# Sensors.net
KiCad netlist of a schematic drawn in Altium Designer
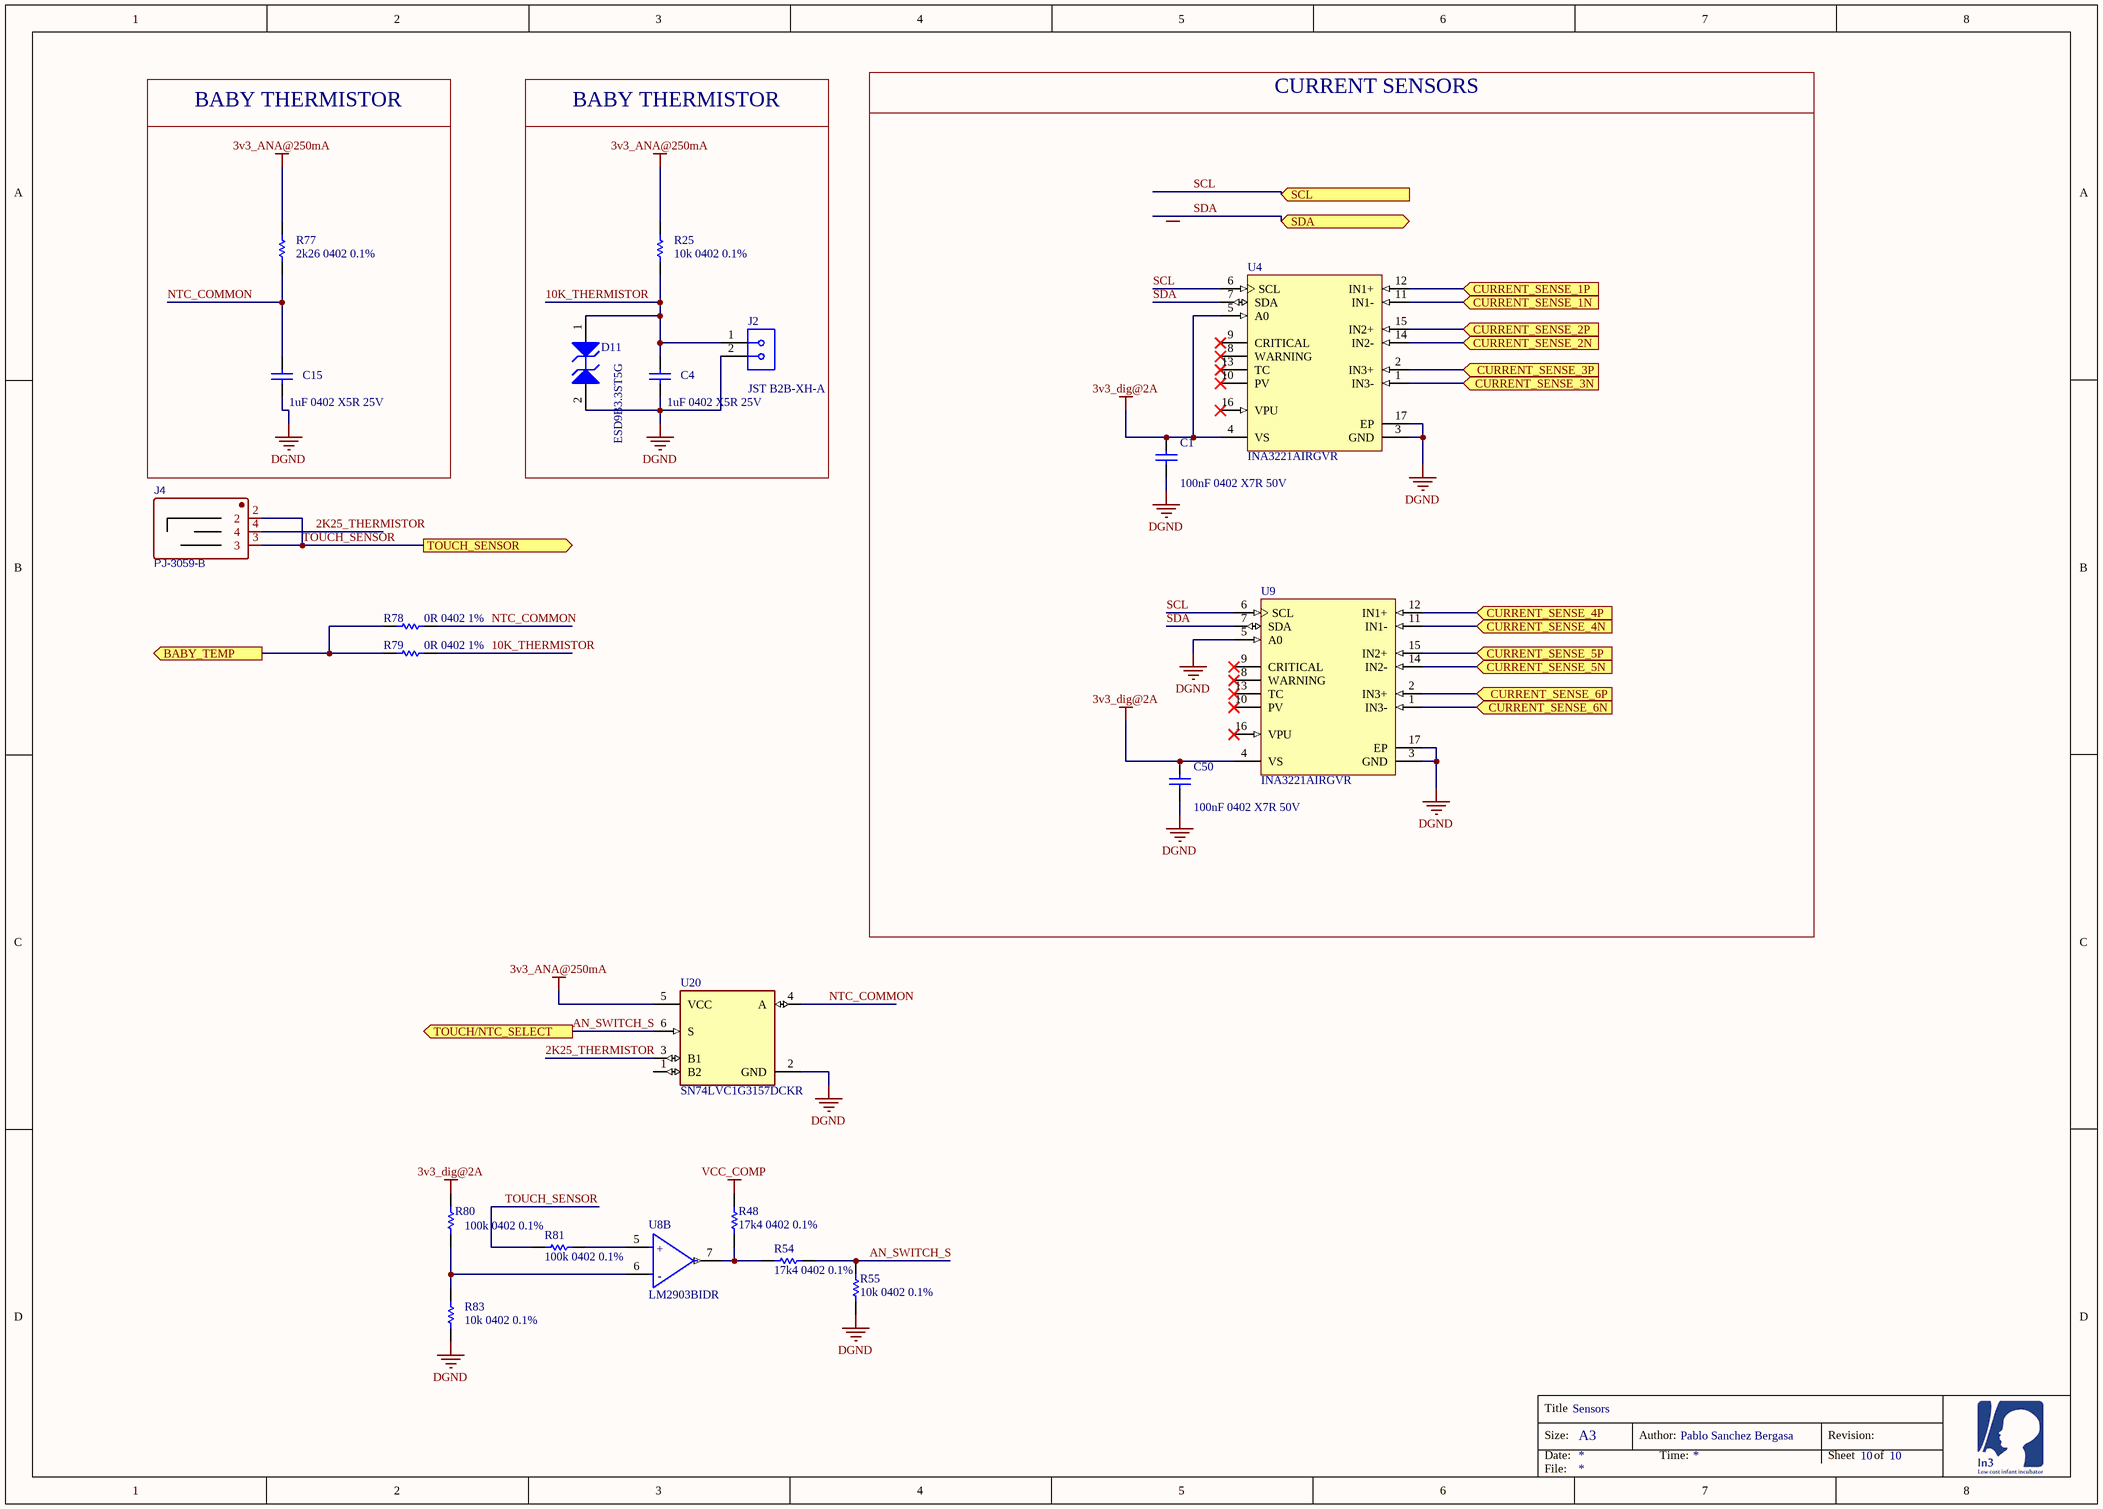
[diagram p0: Sensors.SchDoc]

(export (version "E")
  (design (tool "Eeschema 10.0.6"))
  (components
    (comp (ref "C1")
      (value "100nF 0402 X7R 50V")
      (footprint "CAPC1005X55X25NL5T10")
      (libsource (lib "Altium Content Vault") (part "CAP-NP-2"))
    )
    (comp (ref "C4")
      (value "1uF 0402 X5R 25V")
      (footprint "CAPC1005X55X25NL5T10")
      (libsource (lib "Altium Content Vault") (part "CAP-NP-2"))
    )
    (comp (ref "C15")
      (value "1uF 0402 X5R 25V")
      (footprint "CAPC1005X55X25NL5T10")
      (libsource (lib "Altium Content Vault") (part "CAP-NP-2"))
    )
    (comp (ref "C50")
      (value "100nF 0402 X7R 50V")
      (footprint "CAPC1005X55X25NL5T10")
      (libsource (lib "Altium Content Vault") (part "CAP-NP-2"))
    )
    (comp (ref "D11")
      (value "ESD9B3.3ST5G")
      (footprint "ONSC-SOD-923-2-514AB-01_V")
      (fields (field (name "MANUFACTURER") "On Semiconductor"))
      (libsource (lib "Altium Content Vault") (part "ONSC-A1A2-2"))
    )
    (comp (ref "J2")
      (value "JST B2B-XH-A")
      (footprint "PCB-pp1at3pfx7vls1ur72ey-1")
      (description "Conn Shrouded Header HDR 2 POS 2.5mm Solder ST Thru-Hole Box")
      (fields (field (name "MANUFACTURER PART NUMBER") "B2B-XH-A") (field (name "LCSC PART") "C158012"))
      (libsource (lib "in3ator") (part "CMP-1d67d451da9ec2a0-3"))
    )
    (comp (ref "J4")
      (value "PJ-3059-B")
      (footprint "PJ-3059-B")
      (libsource (lib "jlcpcb_components") (part "PJ-3059-B"))
    )
    (comp (ref "R25")
      (value "10k 0402 0.1%")
      (footprint "RESC1005X40X25ML05T10")
      (libsource (lib "Altium Content Vault") (part "RES"))
    )
    (comp (ref "R48")
      (value "17k4 0402 0.1%")
      (footprint "RESC1005X40X25ML05T10")
      (libsource (lib "Altium Content Vault") (part "RES"))
    )
    (comp (ref "R54")
      (value "17k4 0402 0.1%")
      (footprint "RESC1005X40X25ML05T10")
      (libsource (lib "Altium Content Vault") (part "RES"))
    )
    (comp (ref "R55")
      (value "10k 0402 0.1%")
      (footprint "RESC1005X40X25ML05T10")
      (libsource (lib "Altium Content Vault") (part "RES"))
    )
    (comp (ref "R77")
      (value "2k26 0402 0.1%")
      (footprint "RESC1005X40X25ML05T10")
      (libsource (lib "Altium Content Vault") (part "RES"))
    )
    (comp (ref "R78")
      (value "0R 0402 1%")
      (footprint "RESC1005X40X25ML05T10")
      (libsource (lib "Altium Content Vault") (part "RES"))
    )
    (comp (ref "R79")
      (value "0R 0402 1%")
      (footprint "RESC1005X40X25ML05T10")
      (libsource (lib "Altium Content Vault") (part "RES"))
    )
    (comp (ref "R80")
      (value "100k 0402 0.1%")
      (footprint "RESC1005X40X25ML05T10")
      (libsource (lib "Altium Content Vault") (part "RES"))
    )
    (comp (ref "R81")
      (value "100k 0402 0.1%")
      (footprint "RESC1005X40X25ML05T10")
      (libsource (lib "Altium Content Vault") (part "RES"))
    )
    (comp (ref "R83")
      (value "10k 0402 0.1%")
      (footprint "RESC1005X40X25ML05T10")
      (libsource (lib "Altium Content Vault") (part "RES"))
    )
    (comp (ref "U4")
      (value "INA3221AIRGVR")
      (footprint "RGV0016A_V")
      (fields (field (name "MANUFACTURER") "Texas Instruments"))
      (libsource (lib "Altium Content Vault") (part "TI-INA3221-RGV-16"))
    )
    (comp (ref "U8")
      (value "LM2903BIDR")
      (footprint "FP-D0008A-MFG")
      (description "36V JI.3 DUAL COMPARATOR")
      (fields
        (field (name "OCTOPART") "https://octopart.com/lm2903bidr-texas+instruments-104977165")
        (field (name "MANUFACTURER") "Texas Instruments")
      )
      (libsource (lib "Altium Content Vault") (part "d0dfe35d032f86ae96c0c3919f86c94"))
    )
    (comp (ref "U9")
      (value "INA3221AIRGVR")
      (footprint "RGV0016A_V")
      (fields (field (name "MANUFACTURER") "Texas Instruments"))
      (libsource (lib "Altium Content Vault") (part "TI-INA3221-RGV-16"))
    )
    (comp (ref "U20")
      (value "SN74LVC1G3157DCKR")
      (footprint "FP-DCK0006A-IPC_B")
      (description "IC SWITCH SPDT SC70-6")
      (libsource (lib "Altium Content Vault") (part "0261a57985ab8eeec66806cf7caee19"))
    )
  )
  (nets
    (net (code "1") (name "/2K25_THERMISTOR") (class "Default")
      (node (ref "J4") (pin "4") (pinfunction "4_4") (pintype "passive"))
      (node (ref "U20") (pin "3") (pinfunction "B1_3") (pintype "bidirectional"))
    )
    (net (code "2") (name "/10K_THERMISTOR") (class "Default")
      (node (ref "C4") (pin "2") (pinfunction "2_2") (pintype "passive"))
      (node (ref "D11") (pin "1") (pinfunction "A1_1") (pintype "passive"))
      (node (ref "J2") (pin "1") (pinfunction "1_1") (pintype "passive"))
      (node (ref "R25") (pin "1") (pinfunction "1_1") (pintype "passive"))
      (node (ref "R79") (pin "1") (pinfunction "1_1") (pintype "passive"))
    )
    (net (code "3") (name "/AN_SWITCH_S") (class "Default")
      (node (ref "R54") (pin "2") (pinfunction "2_2") (pintype "passive"))
      (node (ref "R55") (pin "1") (pinfunction "1_1") (pintype "passive"))
      (node (ref "U20") (pin "6") (pinfunction "S_6") (pintype "input"))
    )
    (net (code "4") (name "/BABY_TEMP") (class "Default")
      (node (ref "R78") (pin "2") (pinfunction "2_2") (pintype "passive"))
      (node (ref "R79") (pin "2") (pinfunction "2_2") (pintype "passive"))
    )
    (net (code "5") (name "/CURRENT_SENSE_1N") (class "Default")
      (node (ref "U4") (pin "11") (pinfunction "IN1-_11") (pintype "input"))
    )
    (net (code "6") (name "/CURRENT_SENSE_1P") (class "Default")
      (node (ref "U4") (pin "12") (pinfunction "IN1+_12") (pintype "input"))
    )
    (net (code "7") (name "/CURRENT_SENSE_2N") (class "Default")
      (node (ref "U4") (pin "14") (pinfunction "IN2-_14") (pintype "input"))
    )
    (net (code "8") (name "/CURRENT_SENSE_2P") (class "Default")
      (node (ref "U4") (pin "15") (pinfunction "IN2+_15") (pintype "input"))
    )
    (net (code "9") (name "/CURRENT_SENSE_3N") (class "Default")
      (node (ref "U4") (pin "1") (pinfunction "IN3-_1") (pintype "input"))
    )
    (net (code "10") (name "/CURRENT_SENSE_3P") (class "Default")
      (node (ref "U4") (pin "2") (pinfunction "IN3+_2") (pintype "input"))
    )
    (net (code "11") (name "/CURRENT_SENSE_4N") (class "Default")
      (node (ref "U9") (pin "11") (pinfunction "IN1-_11") (pintype "input"))
    )
    (net (code "12") (name "/CURRENT_SENSE_4P") (class "Default")
      (node (ref "U9") (pin "12") (pinfunction "IN1+_12") (pintype "input"))
    )
    (net (code "13") (name "/CURRENT_SENSE_5N") (class "Default")
      (node (ref "U9") (pin "14") (pinfunction "IN2-_14") (pintype "input"))
    )
    (net (code "14") (name "/CURRENT_SENSE_5P") (class "Default")
      (node (ref "U9") (pin "15") (pinfunction "IN2+_15") (pintype "input"))
    )
    (net (code "15") (name "/CURRENT_SENSE_6N") (class "Default")
      (node (ref "U9") (pin "1") (pinfunction "IN3-_1") (pintype "input"))
    )
    (net (code "16") (name "/CURRENT_SENSE_6P") (class "Default")
      (node (ref "U9") (pin "2") (pinfunction "IN3+_2") (pintype "input"))
    )
    (net (code "17") (name "/NTC_COMMON") (class "Default")
      (node (ref "C15") (pin "2") (pinfunction "2_2") (pintype "passive"))
      (node (ref "R77") (pin "1") (pinfunction "1_1") (pintype "passive"))
      (node (ref "R78") (pin "1") (pinfunction "1_1") (pintype "passive"))
      (node (ref "U20") (pin "4") (pinfunction "A_4") (pintype "bidirectional"))
    )
    (net (code "18") (name "/SCL") (class "Default")
      (node (ref "U4") (pin "6") (pinfunction "SCL_6") (pintype "input"))
      (node (ref "U9") (pin "6") (pinfunction "SCL_6") (pintype "input"))
    )
    (net (code "19") (name "/SDA") (class "Default")
      (node (ref "U4") (pin "7") (pinfunction "SDA_7") (pintype "bidirectional"))
      (node (ref "U9") (pin "7") (pinfunction "SDA_7") (pintype "bidirectional"))
    )
    (net (code "20") (name "/TOUCH_SENSOR") (class "Default")
      (node (ref "J4") (pin "2") (pinfunction "2_2") (pintype "passive"))
      (node (ref "J4") (pin "3") (pinfunction "3_3") (pintype "passive"))
      (node (ref "R81") (pin "2") (pinfunction "2_2") (pintype "passive"))
    )
    (net (code "21") (name "3v3_ANA@250mA") (class "Default")
      (node (ref "R25") (pin "2") (pinfunction "2_2") (pintype "passive"))
      (node (ref "R77") (pin "2") (pinfunction "2_2") (pintype "passive"))
      (node (ref "U20") (pin "5") (pinfunction "VCC_5") (pintype "power_in"))
    )
    (net (code "22") (name "3v3_dig@2A") (class "Default")
      (node (ref "C1") (pin "2") (pinfunction "2_2") (pintype "passive"))
      (node (ref "C50") (pin "2") (pinfunction "2_2") (pintype "passive"))
      (node (ref "R80") (pin "2") (pinfunction "2_2") (pintype "passive"))
      (node (ref "U4") (pin "4") (pinfunction "VS_4") (pintype "power_in"))
      (node (ref "U4") (pin "5") (pinfunction "A0_5") (pintype "input"))
      (node (ref "U9") (pin "4") (pinfunction "VS_4") (pintype "power_in"))
    )
    (net (code "23") (name "DGND") (class "Default")
      (node (ref "C1") (pin "1") (pinfunction "1_1") (pintype "passive"))
      (node (ref "C15") (pin "1") (pinfunction "1_1") (pintype "passive"))
      (node (ref "C4") (pin "1") (pinfunction "1_1") (pintype "passive"))
      (node (ref "C50") (pin "1") (pinfunction "1_1") (pintype "passive"))
      (node (ref "D11") (pin "2") (pinfunction "A2_2") (pintype "passive"))
      (node (ref "J2") (pin "2") (pinfunction "2_2") (pintype "passive"))
      (node (ref "R55") (pin "2") (pinfunction "2_2") (pintype "passive"))
      (node (ref "R83") (pin "1") (pinfunction "1_1") (pintype "passive"))
      (node (ref "U20") (pin "2") (pinfunction "GND_2") (pintype "power_in"))
      (node (ref "U4") (pin "17") (pinfunction "EP_17") (pintype "passive"))
      (node (ref "U4") (pin "3") (pinfunction "GND_3") (pintype "power_in"))
      (node (ref "U9") (pin "17") (pinfunction "EP_17") (pintype "passive"))
      (node (ref "U9") (pin "3") (pinfunction "GND_3") (pintype "power_in"))
      (node (ref "U9") (pin "5") (pinfunction "A0_5") (pintype "input"))
    )
    (net (code "24") (name "Net-(U8B-2IN+)") (class "Default")
      (node (ref "R81") (pin "1") (pinfunction "1_1") (pintype "passive"))
      (node (ref "U8") (pin "5") (pinfunction "2IN+_5") (pintype "tri_state"))
    )
    (net (code "25") (name "Net-(U8B-2IN-)") (class "Default")
      (node (ref "R80") (pin "1") (pinfunction "1_1") (pintype "passive"))
      (node (ref "R83") (pin "2") (pinfunction "2_2") (pintype "passive"))
      (node (ref "U8") (pin "6") (pinfunction "2IN-_6") (pintype "tri_state"))
    )
    (net (code "26") (name "Net-(U8B-2OUT)") (class "Default")
      (node (ref "R48") (pin "1") (pinfunction "1_1") (pintype "passive"))
      (node (ref "R54") (pin "1") (pinfunction "1_1") (pintype "passive"))
      (node (ref "U8") (pin "7") (pinfunction "2OUT_7") (pintype "output"))
    )
    (net (code "27") (name "VCC_COMP") (class "Default")
      (node (ref "R48") (pin "2") (pinfunction "2_2") (pintype "passive"))
    )
    (net (code "28") (name "unconnected-(U4-CRITICAL-Pad9)") (class "Default")
      (node (ref "U4") (pin "9") (pinfunction "CRITICAL_9") (pintype "open_collector+no_connect"))
    )
    (net (code "29") (name "unconnected-(U4-PV-Pad10)") (class "Default")
      (node (ref "U4") (pin "10") (pinfunction "PV_10") (pintype "open_collector+no_connect"))
    )
    (net (code "30") (name "unconnected-(U4-TC-Pad13)") (class "Default")
      (node (ref "U4") (pin "13") (pinfunction "TC_13") (pintype "open_collector+no_connect"))
    )
    (net (code "31") (name "unconnected-(U4-VPU-Pad16)") (class "Default")
      (node (ref "U4") (pin "16") (pinfunction "VPU_16") (pintype "input+no_connect"))
    )
    (net (code "32") (name "unconnected-(U4-WARNING-Pad8)") (class "Default")
      (node (ref "U4") (pin "8") (pinfunction "WARNING_8") (pintype "open_collector+no_connect"))
    )
    (net (code "33") (name "unconnected-(U9-CRITICAL-Pad9)") (class "Default")
      (node (ref "U9") (pin "9") (pinfunction "CRITICAL_9") (pintype "open_collector+no_connect"))
    )
    (net (code "34") (name "unconnected-(U9-PV-Pad10)") (class "Default")
      (node (ref "U9") (pin "10") (pinfunction "PV_10") (pintype "open_collector+no_connect"))
    )
    (net (code "35") (name "unconnected-(U9-TC-Pad13)") (class "Default")
      (node (ref "U9") (pin "13") (pinfunction "TC_13") (pintype "open_collector+no_connect"))
    )
    (net (code "36") (name "unconnected-(U9-VPU-Pad16)") (class "Default")
      (node (ref "U9") (pin "16") (pinfunction "VPU_16") (pintype "input+no_connect"))
    )
    (net (code "37") (name "unconnected-(U9-WARNING-Pad8)") (class "Default")
      (node (ref "U9") (pin "8") (pinfunction "WARNING_8") (pintype "open_collector+no_connect"))
    )
    (net (code "38") (name "unconnected-(U20-B2-Pad1)") (class "Default")
      (node (ref "U20") (pin "1") (pinfunction "B2_1") (pintype "bidirectional"))
    )
  )
)
